# top.net
KiCad netlist of a schematic drawn in Altium Designer
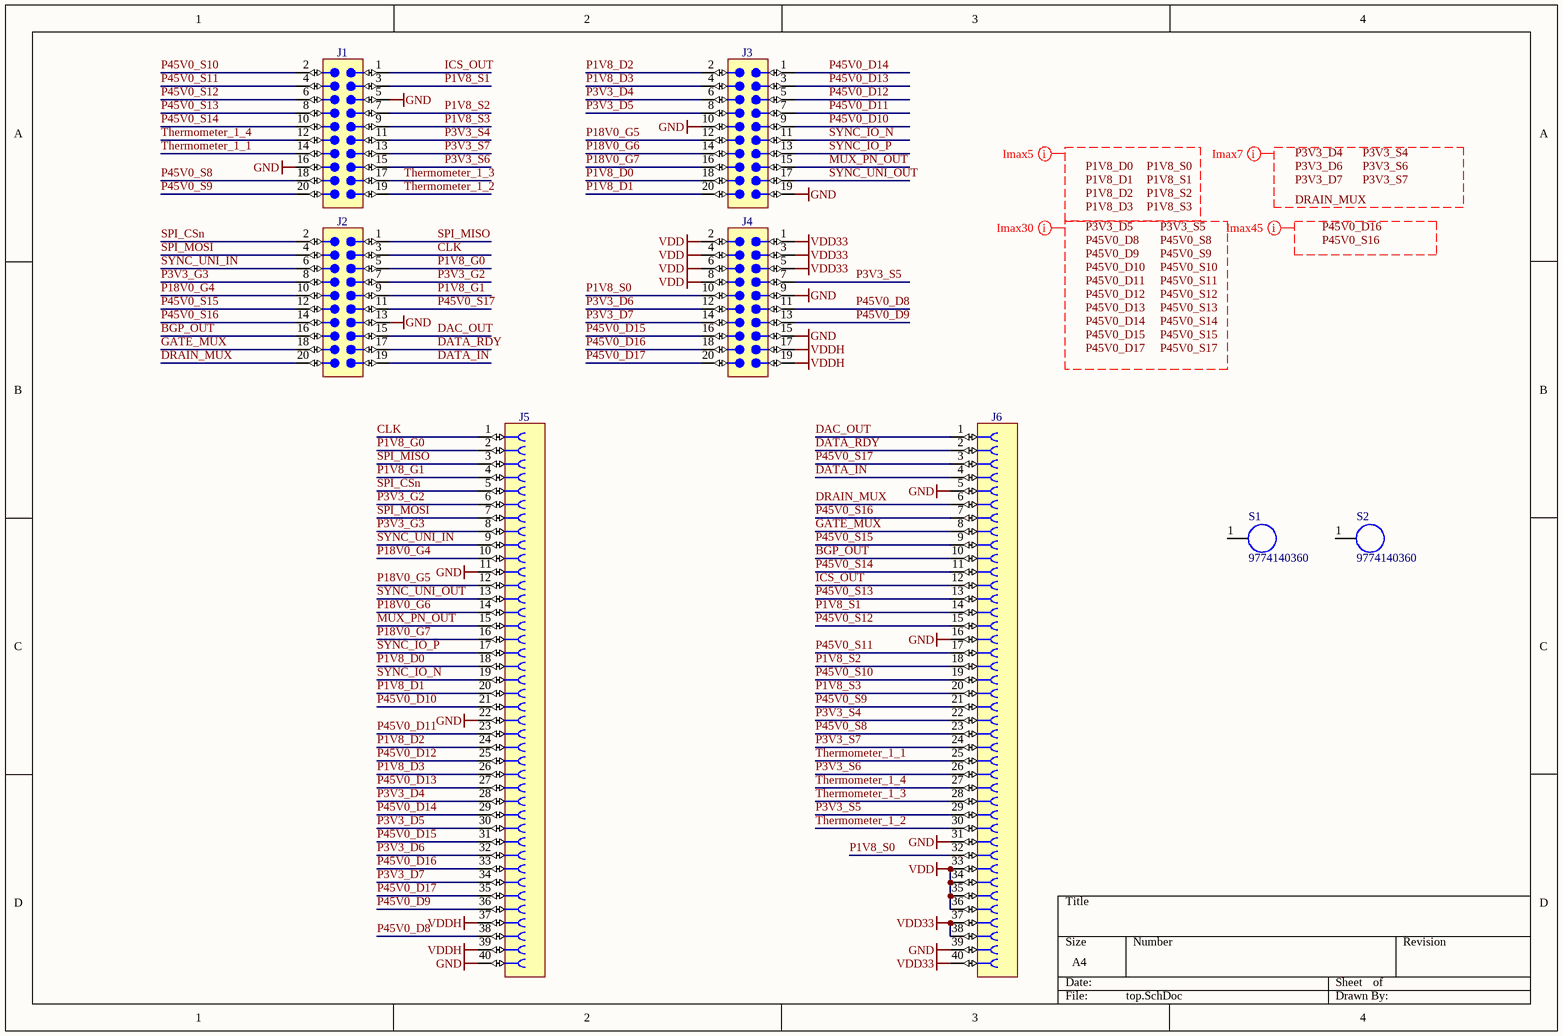
[diagram p0: top.SchDoc]

(export (version "E")
  (design (tool "Eeschema 10.0.6"))
  (components
    (comp (ref "J1")
      (value "Header 20")
      (footprint "3M_45220-600230")
      (description "Connector 20 Male")
      (fields
        (field (name "PART NUMBER") "3M_45220-600230")
        (field (name "MANUFACTURER") "3M")
        (field (name "AUTHOR") "CERN DEM MR")
      )
      (libsource (lib "Connectors") (part "Connector 20 Male"))
    )
    (comp (ref "J2")
      (value "Header 20")
      (footprint "3M_45220-600230")
      (description "Connector 20 Male")
      (fields
        (field (name "PART NUMBER") "3M_45220-600230")
        (field (name "MANUFACTURER") "3M")
        (field (name "AUTHOR") "CERN DEM MR")
      )
      (libsource (lib "Connectors") (part "Connector 20 Male"))
    )
    (comp (ref "J3")
      (value "Header 20")
      (footprint "3M_45220-600230")
      (description "Connector 20 Male")
      (fields
        (field (name "PART NUMBER") "3M_45220-600230")
        (field (name "MANUFACTURER") "3M")
        (field (name "AUTHOR") "CERN DEM MR")
      )
      (libsource (lib "Connectors") (part "Connector 20 Male"))
    )
    (comp (ref "J4")
      (value "Header 20")
      (footprint "3M_45220-600230")
      (description "Connector 20 Male")
      (fields
        (field (name "PART NUMBER") "3M_45220-600230")
        (field (name "MANUFACTURER") "3M")
        (field (name "AUTHOR") "CERN DEM MR")
      )
      (libsource (lib "Connectors") (part "Connector 20 Male"))
    )
    (comp (ref "J5")
      (value "Socket 40")
      (footprint "SAMTEC_RSM-120-02-L-D-K-TR")
      (description "Connector 40 Female")
      (fields
        (field (name "PART NUMBER") "SAMTEC_RSM-120-02-L-D-K-TR")
        (field (name "MANUFACTURER") "SAMTEC")
        (field (name "AUTHOR") "CERN DEM JLC")
      )
      (libsource (lib "Connectors") (part "Connector 40 Female"))
    )
    (comp (ref "J6")
      (value "Socket 40")
      (footprint "SAMTEC_RSM-120-02-L-D-K-TR")
      (description "Connector 40 Female")
      (fields
        (field (name "PART NUMBER") "SAMTEC_RSM-120-02-L-D-K-TR")
        (field (name "MANUFACTURER") "SAMTEC")
        (field (name "AUTHOR") "CERN DEM JLC")
      )
      (libsource (lib "Connectors") (part "Connector 40 Female"))
    )
    (comp (ref "S1")
      (value "9774140360")
      (footprint "9774140360")
      (description "WA-SMSI SMD Steel Spacer with internal Thread")
      (fields (field (name "MANUFACTURER") "Wurth Elektronik") (field (name "CREATED BY") "Baojun Chen"))
      (libsource (lib "Altium_SMSI_SMT_STEEL_SPACER_M2_5_THREAD_INTERNAL_rev15a") (part "WA-SMSI,  9774140360"))
    )
    (comp (ref "S2")
      (value "9774140360")
      (footprint "9774140360")
      (description "WA-SMSI SMD Steel Spacer with internal Thread")
      (fields (field (name "MANUFACTURER") "Wurth Elektronik") (field (name "CREATED BY") "Baojun Chen"))
      (libsource (lib "Altium_SMSI_SMT_STEEL_SPACER_M2_5_THREAD_INTERNAL_rev15a") (part "WA-SMSI,  9774140360"))
    )
  )
  (nets
    (net (code "1") (name "/BGP_OUT") (class "Default")
      (node (ref "J2") (pin "16") (pinfunction "16_16") (pintype "bidirectional"))
      (node (ref "J6") (pin "10") (pinfunction "10_10") (pintype "bidirectional"))
    )
    (net (code "2") (name "/CLK") (class "Default")
      (node (ref "J2") (pin "3") (pinfunction "3_3") (pintype "bidirectional"))
      (node (ref "J5") (pin "1") (pinfunction "1_1") (pintype "bidirectional"))
    )
    (net (code "3") (name "/DAC_OUT") (class "Default")
      (node (ref "J2") (pin "15") (pinfunction "15_15") (pintype "bidirectional"))
      (node (ref "J6") (pin "1") (pinfunction "1_1") (pintype "bidirectional"))
    )
    (net (code "4") (name "/DATA_IN") (class "Default")
      (node (ref "J2") (pin "19") (pinfunction "19_19") (pintype "bidirectional"))
      (node (ref "J6") (pin "4") (pinfunction "4_4") (pintype "bidirectional"))
    )
    (net (code "5") (name "/DATA_RDY") (class "Default")
      (node (ref "J2") (pin "17") (pinfunction "17_17") (pintype "bidirectional"))
      (node (ref "J6") (pin "2") (pinfunction "2_2") (pintype "bidirectional"))
    )
    (net (code "6") (name "/DRAIN_MUX") (class "Default")
      (node (ref "J2") (pin "20") (pinfunction "20_20") (pintype "bidirectional"))
      (node (ref "J6") (pin "6") (pinfunction "6_6") (pintype "bidirectional"))
    )
    (net (code "7") (name "/GATE_MUX") (class "Default")
      (node (ref "J2") (pin "18") (pinfunction "18_18") (pintype "bidirectional"))
      (node (ref "J6") (pin "8") (pinfunction "8_8") (pintype "bidirectional"))
    )
    (net (code "8") (name "/ICS_OUT") (class "Default")
      (node (ref "J1") (pin "1") (pinfunction "1_1") (pintype "bidirectional"))
      (node (ref "J6") (pin "12") (pinfunction "12_12") (pintype "bidirectional"))
    )
    (net (code "9") (name "/MUX_PN_OUT") (class "Default")
      (node (ref "J3") (pin "15") (pinfunction "15_15") (pintype "bidirectional"))
      (node (ref "J5") (pin "15") (pinfunction "15_15") (pintype "bidirectional"))
    )
    (net (code "10") (name "/P1V8_D0") (class "Default")
      (node (ref "J3") (pin "18") (pinfunction "18_18") (pintype "bidirectional"))
      (node (ref "J5") (pin "18") (pinfunction "18_18") (pintype "bidirectional"))
    )
    (net (code "11") (name "/P1V8_D1") (class "Default")
      (node (ref "J3") (pin "20") (pinfunction "20_20") (pintype "bidirectional"))
      (node (ref "J5") (pin "20") (pinfunction "20_20") (pintype "bidirectional"))
    )
    (net (code "12") (name "/P1V8_D2") (class "Default")
      (node (ref "J3") (pin "2") (pinfunction "2_2") (pintype "bidirectional"))
      (node (ref "J5") (pin "24") (pinfunction "24_24") (pintype "bidirectional"))
    )
    (net (code "13") (name "/P1V8_D3") (class "Default")
      (node (ref "J3") (pin "4") (pinfunction "4_4") (pintype "bidirectional"))
      (node (ref "J5") (pin "26") (pinfunction "26_26") (pintype "bidirectional"))
    )
    (net (code "14") (name "/P1V8_G0") (class "Default")
      (node (ref "J2") (pin "5") (pinfunction "5_5") (pintype "bidirectional"))
      (node (ref "J5") (pin "2") (pinfunction "2_2") (pintype "bidirectional"))
    )
    (net (code "15") (name "/P1V8_G1") (class "Default")
      (node (ref "J2") (pin "9") (pinfunction "9_9") (pintype "bidirectional"))
      (node (ref "J5") (pin "4") (pinfunction "4_4") (pintype "bidirectional"))
    )
    (net (code "16") (name "/P1V8_S0") (class "Default")
      (node (ref "J4") (pin "10") (pinfunction "10_10") (pintype "bidirectional"))
      (node (ref "J6") (pin "32") (pinfunction "32_32") (pintype "bidirectional"))
    )
    (net (code "17") (name "/P1V8_S1") (class "Default")
      (node (ref "J1") (pin "3") (pinfunction "3_3") (pintype "bidirectional"))
      (node (ref "J6") (pin "14") (pinfunction "14_14") (pintype "bidirectional"))
    )
    (net (code "18") (name "/P1V8_S2") (class "Default")
      (node (ref "J1") (pin "7") (pinfunction "7_7") (pintype "bidirectional"))
      (node (ref "J6") (pin "18") (pinfunction "18_18") (pintype "bidirectional"))
    )
    (net (code "19") (name "/P1V8_S3") (class "Default")
      (node (ref "J1") (pin "9") (pinfunction "9_9") (pintype "bidirectional"))
      (node (ref "J6") (pin "20") (pinfunction "20_20") (pintype "bidirectional"))
    )
    (net (code "20") (name "/P3V3_D4") (class "Default")
      (node (ref "J3") (pin "6") (pinfunction "6_6") (pintype "bidirectional"))
      (node (ref "J5") (pin "28") (pinfunction "28_28") (pintype "bidirectional"))
    )
    (net (code "21") (name "/P3V3_D5") (class "Default")
      (node (ref "J3") (pin "8") (pinfunction "8_8") (pintype "bidirectional"))
      (node (ref "J5") (pin "30") (pinfunction "30_30") (pintype "bidirectional"))
    )
    (net (code "22") (name "/P3V3_D6") (class "Default")
      (node (ref "J4") (pin "12") (pinfunction "12_12") (pintype "bidirectional"))
      (node (ref "J5") (pin "32") (pinfunction "32_32") (pintype "bidirectional"))
    )
    (net (code "23") (name "/P3V3_D7") (class "Default")
      (node (ref "J4") (pin "14") (pinfunction "14_14") (pintype "bidirectional"))
      (node (ref "J5") (pin "34") (pinfunction "34_34") (pintype "bidirectional"))
    )
    (net (code "24") (name "/P3V3_G2") (class "Default")
      (node (ref "J2") (pin "7") (pinfunction "7_7") (pintype "bidirectional"))
      (node (ref "J5") (pin "6") (pinfunction "6_6") (pintype "bidirectional"))
    )
    (net (code "25") (name "/P3V3_G3") (class "Default")
      (node (ref "J2") (pin "8") (pinfunction "8_8") (pintype "bidirectional"))
      (node (ref "J5") (pin "8") (pinfunction "8_8") (pintype "bidirectional"))
    )
    (net (code "26") (name "/P3V3_S4") (class "Default")
      (node (ref "J1") (pin "11") (pinfunction "11_11") (pintype "bidirectional"))
      (node (ref "J6") (pin "22") (pinfunction "22_22") (pintype "bidirectional"))
    )
    (net (code "27") (name "/P3V3_S5") (class "Default")
      (node (ref "J4") (pin "7") (pinfunction "7_7") (pintype "bidirectional"))
      (node (ref "J6") (pin "29") (pinfunction "29_29") (pintype "bidirectional"))
    )
    (net (code "28") (name "/P3V3_S6") (class "Default")
      (node (ref "J1") (pin "15") (pinfunction "15_15") (pintype "bidirectional"))
      (node (ref "J6") (pin "26") (pinfunction "26_26") (pintype "bidirectional"))
    )
    (net (code "29") (name "/P3V3_S7") (class "Default")
      (node (ref "J1") (pin "13") (pinfunction "13_13") (pintype "bidirectional"))
      (node (ref "J6") (pin "24") (pinfunction "24_24") (pintype "bidirectional"))
    )
    (net (code "30") (name "/P18V0_G4") (class "Default")
      (node (ref "J2") (pin "10") (pinfunction "10_10") (pintype "bidirectional"))
      (node (ref "J5") (pin "10") (pinfunction "10_10") (pintype "bidirectional"))
    )
    (net (code "31") (name "/P18V0_G5") (class "Default")
      (node (ref "J3") (pin "12") (pinfunction "12_12") (pintype "bidirectional"))
      (node (ref "J5") (pin "12") (pinfunction "12_12") (pintype "bidirectional"))
    )
    (net (code "32") (name "/P18V0_G6") (class "Default")
      (node (ref "J3") (pin "14") (pinfunction "14_14") (pintype "bidirectional"))
      (node (ref "J5") (pin "14") (pinfunction "14_14") (pintype "bidirectional"))
    )
    (net (code "33") (name "/P18V0_G7") (class "Default")
      (node (ref "J3") (pin "16") (pinfunction "16_16") (pintype "bidirectional"))
      (node (ref "J5") (pin "16") (pinfunction "16_16") (pintype "bidirectional"))
    )
    (net (code "34") (name "/P45V0_D8") (class "Default")
      (node (ref "J4") (pin "11") (pinfunction "11_11") (pintype "bidirectional"))
      (node (ref "J5") (pin "38") (pinfunction "38_38") (pintype "bidirectional"))
    )
    (net (code "35") (name "/P45V0_D9") (class "Default")
      (node (ref "J4") (pin "13") (pinfunction "13_13") (pintype "bidirectional"))
      (node (ref "J5") (pin "36") (pinfunction "36_36") (pintype "bidirectional"))
    )
    (net (code "36") (name "/P45V0_D10") (class "Default")
      (node (ref "J3") (pin "9") (pinfunction "9_9") (pintype "bidirectional"))
      (node (ref "J5") (pin "21") (pinfunction "21_21") (pintype "bidirectional"))
    )
    (net (code "37") (name "/P45V0_D11") (class "Default")
      (node (ref "J3") (pin "7") (pinfunction "7_7") (pintype "bidirectional"))
      (node (ref "J5") (pin "23") (pinfunction "23_23") (pintype "bidirectional"))
    )
    (net (code "38") (name "/P45V0_D12") (class "Default")
      (node (ref "J3") (pin "5") (pinfunction "5_5") (pintype "bidirectional"))
      (node (ref "J5") (pin "25") (pinfunction "25_25") (pintype "bidirectional"))
    )
    (net (code "39") (name "/P45V0_D13") (class "Default")
      (node (ref "J3") (pin "3") (pinfunction "3_3") (pintype "bidirectional"))
      (node (ref "J5") (pin "27") (pinfunction "27_27") (pintype "bidirectional"))
    )
    (net (code "40") (name "/P45V0_D14") (class "Default")
      (node (ref "J3") (pin "1") (pinfunction "1_1") (pintype "bidirectional"))
      (node (ref "J5") (pin "29") (pinfunction "29_29") (pintype "bidirectional"))
    )
    (net (code "41") (name "/P45V0_D15") (class "Default")
      (node (ref "J4") (pin "16") (pinfunction "16_16") (pintype "bidirectional"))
      (node (ref "J5") (pin "31") (pinfunction "31_31") (pintype "bidirectional"))
    )
    (net (code "42") (name "/P45V0_D16") (class "Default")
      (node (ref "J4") (pin "18") (pinfunction "18_18") (pintype "bidirectional"))
      (node (ref "J5") (pin "33") (pinfunction "33_33") (pintype "bidirectional"))
    )
    (net (code "43") (name "/P45V0_D17") (class "Default")
      (node (ref "J4") (pin "20") (pinfunction "20_20") (pintype "bidirectional"))
      (node (ref "J5") (pin "35") (pinfunction "35_35") (pintype "bidirectional"))
    )
    (net (code "44") (name "/P45V0_S8") (class "Default")
      (node (ref "J1") (pin "18") (pinfunction "18_18") (pintype "bidirectional"))
      (node (ref "J6") (pin "23") (pinfunction "23_23") (pintype "bidirectional"))
    )
    (net (code "45") (name "/P45V0_S9") (class "Default")
      (node (ref "J1") (pin "20") (pinfunction "20_20") (pintype "bidirectional"))
      (node (ref "J6") (pin "21") (pinfunction "21_21") (pintype "bidirectional"))
    )
    (net (code "46") (name "/P45V0_S10") (class "Default")
      (node (ref "J1") (pin "2") (pinfunction "2_2") (pintype "bidirectional"))
      (node (ref "J6") (pin "19") (pinfunction "19_19") (pintype "bidirectional"))
    )
    (net (code "47") (name "/P45V0_S11") (class "Default")
      (node (ref "J1") (pin "4") (pinfunction "4_4") (pintype "bidirectional"))
      (node (ref "J6") (pin "17") (pinfunction "17_17") (pintype "bidirectional"))
    )
    (net (code "48") (name "/P45V0_S12") (class "Default")
      (node (ref "J1") (pin "6") (pinfunction "6_6") (pintype "bidirectional"))
      (node (ref "J6") (pin "15") (pinfunction "15_15") (pintype "bidirectional"))
    )
    (net (code "49") (name "/P45V0_S13") (class "Default")
      (node (ref "J1") (pin "8") (pinfunction "8_8") (pintype "bidirectional"))
      (node (ref "J6") (pin "13") (pinfunction "13_13") (pintype "bidirectional"))
    )
    (net (code "50") (name "/P45V0_S14") (class "Default")
      (node (ref "J1") (pin "10") (pinfunction "10_10") (pintype "bidirectional"))
      (node (ref "J6") (pin "11") (pinfunction "11_11") (pintype "bidirectional"))
    )
    (net (code "51") (name "/P45V0_S15") (class "Default")
      (node (ref "J2") (pin "12") (pinfunction "12_12") (pintype "bidirectional"))
      (node (ref "J6") (pin "9") (pinfunction "9_9") (pintype "bidirectional"))
    )
    (net (code "52") (name "/P45V0_S16") (class "Default")
      (node (ref "J2") (pin "14") (pinfunction "14_14") (pintype "bidirectional"))
      (node (ref "J6") (pin "7") (pinfunction "7_7") (pintype "bidirectional"))
    )
    (net (code "53") (name "/P45V0_S17") (class "Default")
      (node (ref "J2") (pin "11") (pinfunction "11_11") (pintype "bidirectional"))
      (node (ref "J6") (pin "3") (pinfunction "3_3") (pintype "bidirectional"))
    )
    (net (code "54") (name "/SPI_CSn") (class "Default")
      (node (ref "J2") (pin "2") (pinfunction "2_2") (pintype "bidirectional"))
      (node (ref "J5") (pin "5") (pinfunction "5_5") (pintype "bidirectional"))
    )
    (net (code "55") (name "/SPI_MISO") (class "Default")
      (node (ref "J2") (pin "1") (pinfunction "1_1") (pintype "bidirectional"))
      (node (ref "J5") (pin "3") (pinfunction "3_3") (pintype "bidirectional"))
    )
    (net (code "56") (name "/SPI_MOSI") (class "Default")
      (node (ref "J2") (pin "4") (pinfunction "4_4") (pintype "bidirectional"))
      (node (ref "J5") (pin "7") (pinfunction "7_7") (pintype "bidirectional"))
    )
    (net (code "57") (name "/SYNC_IO_N") (class "Default")
      (node (ref "J3") (pin "11") (pinfunction "11_11") (pintype "bidirectional"))
      (node (ref "J5") (pin "19") (pinfunction "19_19") (pintype "bidirectional"))
    )
    (net (code "58") (name "/SYNC_IO_P") (class "Default")
      (node (ref "J3") (pin "13") (pinfunction "13_13") (pintype "bidirectional"))
      (node (ref "J5") (pin "17") (pinfunction "17_17") (pintype "bidirectional"))
    )
    (net (code "59") (name "/SYNC_UNI_IN") (class "Default")
      (node (ref "J2") (pin "6") (pinfunction "6_6") (pintype "bidirectional"))
      (node (ref "J5") (pin "9") (pinfunction "9_9") (pintype "bidirectional"))
    )
    (net (code "60") (name "/SYNC_UNI_OUT") (class "Default")
      (node (ref "J3") (pin "17") (pinfunction "17_17") (pintype "bidirectional"))
      (node (ref "J5") (pin "13") (pinfunction "13_13") (pintype "bidirectional"))
    )
    (net (code "61") (name "/Thermometer_1_1") (class "Default")
      (node (ref "J1") (pin "14") (pinfunction "14_14") (pintype "bidirectional"))
      (node (ref "J6") (pin "25") (pinfunction "25_25") (pintype "bidirectional"))
    )
    (net (code "62") (name "/Thermometer_1_2") (class "Default")
      (node (ref "J1") (pin "19") (pinfunction "19_19") (pintype "bidirectional"))
      (node (ref "J6") (pin "30") (pinfunction "30_30") (pintype "bidirectional"))
    )
    (net (code "63") (name "/Thermometer_1_3") (class "Default")
      (node (ref "J1") (pin "17") (pinfunction "17_17") (pintype "bidirectional"))
      (node (ref "J6") (pin "28") (pinfunction "28_28") (pintype "bidirectional"))
    )
    (net (code "64") (name "/Thermometer_1_4") (class "Default")
      (node (ref "J1") (pin "12") (pinfunction "12_12") (pintype "bidirectional"))
      (node (ref "J6") (pin "27") (pinfunction "27_27") (pintype "bidirectional"))
    )
    (net (code "65") (name "GND") (class "Default")
      (node (ref "J1") (pin "16") (pinfunction "16_16") (pintype "bidirectional"))
      (node (ref "J1") (pin "5") (pinfunction "5_5") (pintype "bidirectional"))
      (node (ref "J2") (pin "13") (pinfunction "13_13") (pintype "bidirectional"))
      (node (ref "J3") (pin "10") (pinfunction "10_10") (pintype "bidirectional"))
      (node (ref "J3") (pin "19") (pinfunction "19_19") (pintype "bidirectional"))
      (node (ref "J4") (pin "15") (pinfunction "15_15") (pintype "bidirectional"))
      (node (ref "J4") (pin "9") (pinfunction "9_9") (pintype "bidirectional"))
      (node (ref "J5") (pin "11") (pinfunction "11_11") (pintype "bidirectional"))
      (node (ref "J5") (pin "22") (pinfunction "22_22") (pintype "bidirectional"))
      (node (ref "J5") (pin "40") (pinfunction "40_40") (pintype "bidirectional"))
      (node (ref "J6") (pin "16") (pinfunction "16_16") (pintype "bidirectional"))
      (node (ref "J6") (pin "31") (pinfunction "31_31") (pintype "bidirectional"))
      (node (ref "J6") (pin "39") (pinfunction "39_39") (pintype "bidirectional"))
      (node (ref "J6") (pin "5") (pinfunction "5_5") (pintype "bidirectional"))
    )
    (net (code "66") (name "VDD") (class "Default")
      (node (ref "J4") (pin "2") (pinfunction "2_2") (pintype "bidirectional"))
      (node (ref "J4") (pin "4") (pinfunction "4_4") (pintype "bidirectional"))
      (node (ref "J4") (pin "6") (pinfunction "6_6") (pintype "bidirectional"))
      (node (ref "J4") (pin "8") (pinfunction "8_8") (pintype "bidirectional"))
      (node (ref "J6") (pin "33") (pinfunction "33_33") (pintype "bidirectional"))
      (node (ref "J6") (pin "34") (pinfunction "34_34") (pintype "bidirectional"))
      (node (ref "J6") (pin "35") (pinfunction "35_35") (pintype "bidirectional"))
      (node (ref "J6") (pin "36") (pinfunction "36_36") (pintype "bidirectional"))
    )
    (net (code "67") (name "VDD33") (class "Default")
      (node (ref "J4") (pin "1") (pinfunction "1_1") (pintype "bidirectional"))
      (node (ref "J4") (pin "3") (pinfunction "3_3") (pintype "bidirectional"))
      (node (ref "J4") (pin "5") (pinfunction "5_5") (pintype "bidirectional"))
      (node (ref "J6") (pin "37") (pinfunction "37_37") (pintype "bidirectional"))
      (node (ref "J6") (pin "38") (pinfunction "38_38") (pintype "bidirectional"))
      (node (ref "J6") (pin "40") (pinfunction "40_40") (pintype "bidirectional"))
    )
    (net (code "68") (name "VDDH") (class "Default")
      (node (ref "J4") (pin "17") (pinfunction "17_17") (pintype "bidirectional"))
      (node (ref "J4") (pin "19") (pinfunction "19_19") (pintype "bidirectional"))
      (node (ref "J5") (pin "37") (pinfunction "37_37") (pintype "bidirectional"))
      (node (ref "J5") (pin "39") (pinfunction "39_39") (pintype "bidirectional"))
    )
    (net (code "69") (name "unconnected-(S1-Pad1)") (class "Default")
      (node (ref "S1") (pin "1") (pinfunction "1_1") (pintype "passive"))
    )
    (net (code "70") (name "unconnected-(S2-Pad1)") (class "Default")
      (node (ref "S2") (pin "1") (pinfunction "1_1") (pintype "passive"))
    )
  )
)
